# hoppercontroller.net
KiCad netlist of a schematic drawn in EAGLE
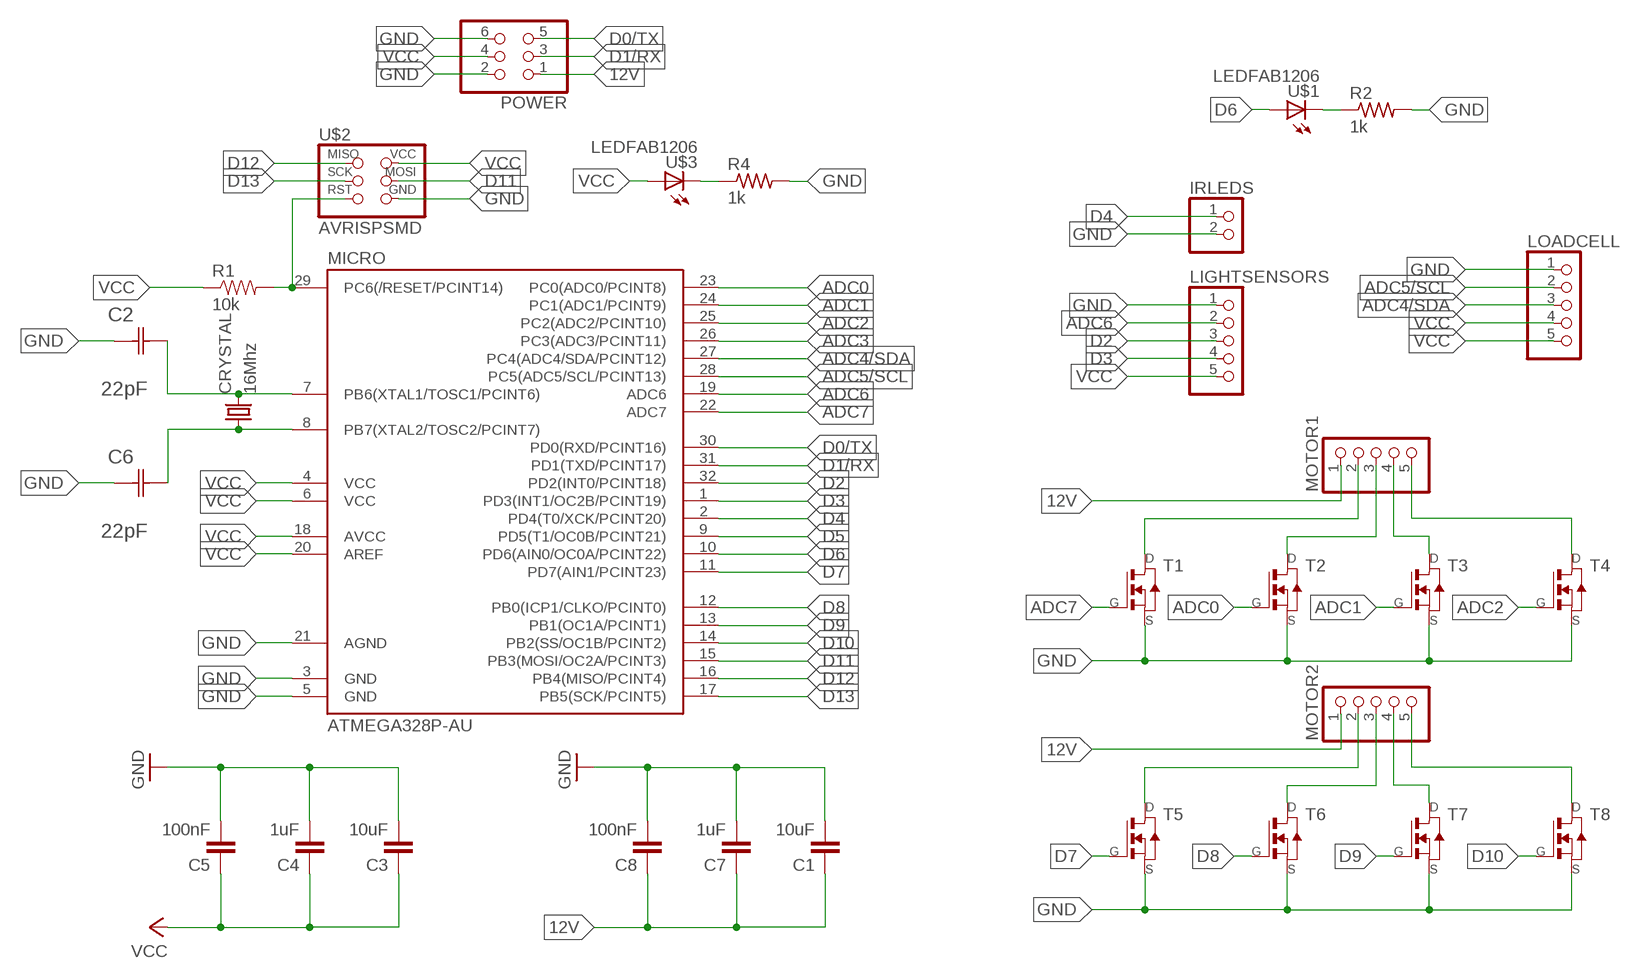
[diagram p0: schematic, sheet 1]

(export (version "E")
  (design (tool "Eeschema 10.0.6"))
  (components
    (comp (ref "C1")
      (value "10uF")
      (footprint "eagle-import:1206")
      (libsource (lib "eagle-import") (part "CAP1206"))
    )
    (comp (ref "C2")
      (value "22pF")
      (footprint "eagle-import:CAPC3216X178N")
      (fields (field (name "MPN") "0612ZC225MAT2A") (field (name "TOLERANCE") "±20%"))
      (libsource (lib "eagle-import") (part "0612ZC225MAT2A"))
    )
    (comp (ref "C3")
      (value "10uF")
      (footprint "eagle-import:1206")
      (libsource (lib "eagle-import") (part "CAP1206"))
    )
    (comp (ref "C4")
      (value "1uF")
      (footprint "eagle-import:1206")
      (libsource (lib "eagle-import") (part "CAP1206"))
    )
    (comp (ref "C5")
      (value "100nF")
      (footprint "eagle-import:1206")
      (libsource (lib "eagle-import") (part "CAP1206"))
    )
    (comp (ref "C6")
      (value "22pF")
      (footprint "eagle-import:CAPC3216X178N")
      (fields (field (name "MPN") "0612ZC225MAT2A") (field (name "TOLERANCE") "±20%"))
      (libsource (lib "eagle-import") (part "0612ZC225MAT2A"))
    )
    (comp (ref "C7")
      (value "1uF")
      (footprint "eagle-import:1206")
      (libsource (lib "eagle-import") (part "CAP1206"))
    )
    (comp (ref "C8")
      (value "100nF")
      (footprint "eagle-import:1206")
      (libsource (lib "eagle-import") (part "CAP1206"))
    )
    (comp (ref "CRYSTAL")
      (value "16Mhz")
      (footprint "eagle-import:CSM-7X-DU")
      (libsource (lib "eagle-import") (part "CSM-7X-DU"))
    )
    (comp (ref "IRLEDS")
      (value "PINHD-1X2")
      (footprint "eagle-import:1X02")
      (libsource (lib "eagle-import") (part "PINHD-1X2"))
    )
    (comp (ref "LIGHTSENSORS")
      (value "PINHD-1X5")
      (footprint "eagle-import:1X05")
      (libsource (lib "eagle-import") (part "PINHD-1X5"))
    )
    (comp (ref "LOADCELL")
      (value "PINHD-1X5")
      (footprint "eagle-import:1X05")
      (libsource (lib "eagle-import") (part "PINHD-1X5"))
    )
    (comp (ref "MICRO")
      (value "ATMEGA328P-AU")
      (footprint "eagle-import:TQFP32-08")
      (libsource (lib "eagle-import") (part "ATMEGA48/88/168-AU"))
    )
    (comp (ref "MOTOR1")
      (value "PINHD-1X5")
      (footprint "eagle-import:1X05")
      (libsource (lib "eagle-import") (part "PINHD-1X5"))
    )
    (comp (ref "MOTOR2")
      (value "PINHD-1X5")
      (footprint "eagle-import:1X05")
      (libsource (lib "eagle-import") (part "PINHD-1X5"))
    )
    (comp (ref "POWER")
      (value "PINHD-2X3-SMD")
      (footprint "eagle-import:2X03SMD")
      (libsource (lib "eagle-import") (part "PINHD-2X3-SMD"))
    )
    (comp (ref "R1")
      (value "10k")
      (footprint "eagle-import:1206")
      (libsource (lib "eagle-import") (part "RESISTOR1206"))
    )
    (comp (ref "R2")
      (value "1k")
      (footprint "eagle-import:R1206FAB")
      (libsource (lib "eagle-import") (part "RES-US1206FAB"))
    )
    (comp (ref "R4")
      (value "1k")
      (footprint "eagle-import:R1206FAB")
      (libsource (lib "eagle-import") (part "RES-US1206FAB"))
    )
    (comp (ref "T1")
      (value "NMOSFETTO252")
      (footprint "eagle-import:TO252")
      (libsource (lib "eagle-import") (part "NMOSFETTO252"))
    )
    (comp (ref "T2")
      (value "NMOSFETTO252")
      (footprint "eagle-import:TO252")
      (libsource (lib "eagle-import") (part "NMOSFETTO252"))
    )
    (comp (ref "T3")
      (value "NMOSFETTO252")
      (footprint "eagle-import:TO252")
      (libsource (lib "eagle-import") (part "NMOSFETTO252"))
    )
    (comp (ref "T4")
      (value "NMOSFETTO252")
      (footprint "eagle-import:TO252")
      (libsource (lib "eagle-import") (part "NMOSFETTO252"))
    )
    (comp (ref "T5")
      (value "NMOSFETTO252")
      (footprint "eagle-import:TO252")
      (libsource (lib "eagle-import") (part "NMOSFETTO252"))
    )
    (comp (ref "T6")
      (value "NMOSFETTO252")
      (footprint "eagle-import:TO252")
      (libsource (lib "eagle-import") (part "NMOSFETTO252"))
    )
    (comp (ref "T7")
      (value "NMOSFETTO252")
      (footprint "eagle-import:TO252")
      (libsource (lib "eagle-import") (part "NMOSFETTO252"))
    )
    (comp (ref "T8")
      (value "NMOSFETTO252")
      (footprint "eagle-import:TO252")
      (libsource (lib "eagle-import") (part "NMOSFETTO252"))
    )
    (comp (ref "U$1")
      (value "LEDFAB1206")
      (footprint "eagle-import:LED1206FAB")
      (libsource (lib "eagle-import") (part "LEDFAB1206"))
    )
    (comp (ref "U$2")
      (value "AVRISPSMD")
      (footprint "eagle-import:2X03SMD")
      (libsource (lib "eagle-import") (part "AVRISPSMD"))
    )
    (comp (ref "U$3")
      (value "LEDFAB1206")
      (footprint "eagle-import:LED1206FAB")
      (libsource (lib "eagle-import") (part "LEDFAB1206"))
    )
  )
  (nets
    (net (code "1") (name "12V") (class "Default")
      (node (ref "C1") (pin "1") (pinfunction "1_1") (pintype "passive"))
      (node (ref "C7") (pin "1") (pinfunction "1_1") (pintype "passive"))
      (node (ref "C8") (pin "1") (pinfunction "1_1") (pintype "passive"))
      (node (ref "MOTOR1") (pin "1") (pinfunction "1_1") (pintype "passive"))
      (node (ref "MOTOR2") (pin "1") (pinfunction "1_1") (pintype "passive"))
      (node (ref "POWER") (pin "1") (pinfunction "1_1") (pintype "passive"))
    )
    (net (code "2") (name "ADC0") (class "Default")
      (node (ref "MICRO") (pin "23") (pinfunction "PC0(ADC0/PCINT8)_23") (pintype "bidirectional"))
      (node (ref "T2") (pin "1") (pinfunction "G_1") (pintype "passive"))
    )
    (net (code "3") (name "ADC1") (class "Default")
      (node (ref "MICRO") (pin "24") (pinfunction "PC1(ADC1/PCINT9)_24") (pintype "bidirectional"))
      (node (ref "T3") (pin "1") (pinfunction "G_1") (pintype "passive"))
    )
    (net (code "4") (name "ADC2") (class "Default")
      (node (ref "MICRO") (pin "25") (pinfunction "PC2(ADC2/PCINT10)_25") (pintype "bidirectional"))
      (node (ref "T4") (pin "1") (pinfunction "G_1") (pintype "passive"))
    )
    (net (code "5") (name "ADC3") (class "Default")
      (node (ref "MICRO") (pin "26") (pinfunction "PC3(ADC3/PCINT11)_26") (pintype "bidirectional"))
    )
    (net (code "6") (name "ADC4{slash}SDA") (class "Default")
      (node (ref "LOADCELL") (pin "3") (pinfunction "3_3") (pintype "passive"))
      (node (ref "MICRO") (pin "27") (pinfunction "PC4(ADC4/SDA/PCINT12)_27") (pintype "bidirectional"))
    )
    (net (code "7") (name "ADC5{slash}SCL") (class "Default")
      (node (ref "LOADCELL") (pin "2") (pinfunction "2_2") (pintype "passive"))
      (node (ref "MICRO") (pin "28") (pinfunction "PC5(ADC5/SCL/PCINT13)_28") (pintype "bidirectional"))
    )
    (net (code "8") (name "ADC6") (class "Default")
      (node (ref "LIGHTSENSORS") (pin "2") (pinfunction "2_2") (pintype "passive"))
      (node (ref "MICRO") (pin "19") (pinfunction "ADC6_19") (pintype "passive"))
    )
    (net (code "9") (name "ADC7") (class "Default")
      (node (ref "MICRO") (pin "22") (pinfunction "ADC7_22") (pintype "passive"))
      (node (ref "T1") (pin "1") (pinfunction "G_1") (pintype "passive"))
    )
    (net (code "10") (name "D0{slash}TX") (class "Default")
      (node (ref "MICRO") (pin "30") (pinfunction "PD0(RXD/PCINT16)_30") (pintype "bidirectional"))
      (node (ref "POWER") (pin "5") (pinfunction "5_5") (pintype "passive"))
    )
    (net (code "11") (name "D1{slash}RX") (class "Default")
      (node (ref "MICRO") (pin "31") (pinfunction "PD1(TXD/PCINT17)_31") (pintype "bidirectional"))
      (node (ref "POWER") (pin "3") (pinfunction "3_3") (pintype "passive"))
    )
    (net (code "12") (name "D2") (class "Default")
      (node (ref "LIGHTSENSORS") (pin "3") (pinfunction "3_3") (pintype "passive"))
      (node (ref "MICRO") (pin "32") (pinfunction "PD2(INT0/PCINT18)_32") (pintype "bidirectional"))
    )
    (net (code "13") (name "D3") (class "Default")
      (node (ref "LIGHTSENSORS") (pin "4") (pinfunction "4_4") (pintype "passive"))
      (node (ref "MICRO") (pin "1") (pinfunction "PD3(INT1/OC2B/PCINT19)_1") (pintype "bidirectional"))
    )
    (net (code "14") (name "D4") (class "Default")
      (node (ref "IRLEDS") (pin "1") (pinfunction "1_1") (pintype "passive"))
      (node (ref "MICRO") (pin "2") (pinfunction "PD4(T0/XCK/PCINT20)_2") (pintype "bidirectional"))
    )
    (net (code "15") (name "D5") (class "Default")
      (node (ref "MICRO") (pin "9") (pinfunction "PD5(T1/OC0B/PCINT21)_9") (pintype "bidirectional"))
    )
    (net (code "16") (name "D6") (class "Default")
      (node (ref "MICRO") (pin "10") (pinfunction "PD6(AIN0/OC0A/PCINT22)_10") (pintype "bidirectional"))
      (node (ref "U$1") (pin "1") (pinfunction "A_1") (pintype "passive"))
    )
    (net (code "17") (name "D7") (class "Default")
      (node (ref "MICRO") (pin "11") (pinfunction "PD7(AIN1/PCINT23)_11") (pintype "bidirectional"))
      (node (ref "T5") (pin "1") (pinfunction "G_1") (pintype "passive"))
    )
    (net (code "18") (name "D8") (class "Default")
      (node (ref "MICRO") (pin "12") (pinfunction "PB0(ICP1/CLKO/PCINT0)_12") (pintype "bidirectional"))
      (node (ref "T6") (pin "1") (pinfunction "G_1") (pintype "passive"))
    )
    (net (code "19") (name "D9") (class "Default")
      (node (ref "MICRO") (pin "13") (pinfunction "PB1(OC1A/PCINT1)_13") (pintype "bidirectional"))
      (node (ref "T7") (pin "1") (pinfunction "G_1") (pintype "passive"))
    )
    (net (code "20") (name "D10") (class "Default")
      (node (ref "MICRO") (pin "14") (pinfunction "PB2(SS/OC1B/PCINT2)_14") (pintype "bidirectional"))
      (node (ref "T8") (pin "1") (pinfunction "G_1") (pintype "passive"))
    )
    (net (code "21") (name "D11") (class "Default")
      (node (ref "MICRO") (pin "15") (pinfunction "PB3(MOSI/OC2A/PCINT3)_15") (pintype "bidirectional"))
      (node (ref "U$2") (pin "4") (pinfunction "MOSI_4") (pintype "passive"))
    )
    (net (code "22") (name "D12") (class "Default")
      (node (ref "MICRO") (pin "16") (pinfunction "PB4(MISO/PCINT4)_16") (pintype "bidirectional"))
      (node (ref "U$2") (pin "1") (pinfunction "MISO_1") (pintype "passive"))
    )
    (net (code "23") (name "D13") (class "Default")
      (node (ref "MICRO") (pin "17") (pinfunction "PB5(SCK/PCINT5)_17") (pintype "bidirectional"))
      (node (ref "U$2") (pin "3") (pinfunction "SCK_3") (pintype "passive"))
    )
    (net (code "24") (name "GND") (class "Default")
      (node (ref "C1") (pin "2") (pinfunction "2_2") (pintype "passive"))
      (node (ref "C2") (pin "1") (pinfunction "C1_1") (pintype "passive"))
      (node (ref "C3") (pin "2") (pinfunction "2_2") (pintype "passive"))
      (node (ref "C4") (pin "2") (pinfunction "2_2") (pintype "passive"))
      (node (ref "C5") (pin "2") (pinfunction "2_2") (pintype "passive"))
      (node (ref "C6") (pin "1") (pinfunction "C1_1") (pintype "passive"))
      (node (ref "C7") (pin "2") (pinfunction "2_2") (pintype "passive"))
      (node (ref "C8") (pin "2") (pinfunction "2_2") (pintype "passive"))
      (node (ref "IRLEDS") (pin "2") (pinfunction "2_2") (pintype "passive"))
      (node (ref "LIGHTSENSORS") (pin "1") (pinfunction "1_1") (pintype "passive"))
      (node (ref "LOADCELL") (pin "1") (pinfunction "1_1") (pintype "passive"))
      (node (ref "MICRO") (pin "21") (pinfunction "AGND_21") (pintype "power_in"))
      (node (ref "MICRO") (pin "3") (pinfunction "GND_3") (pintype "power_in"))
      (node (ref "MICRO") (pin "5") (pinfunction "GND_5") (pintype "power_in"))
      (node (ref "POWER") (pin "2") (pinfunction "2_2") (pintype "passive"))
      (node (ref "POWER") (pin "6") (pinfunction "6_6") (pintype "passive"))
      (node (ref "R2") (pin "2") (pinfunction "2_2") (pintype "passive"))
      (node (ref "R4") (pin "2") (pinfunction "2_2") (pintype "passive"))
      (node (ref "T1") (pin "2") (pinfunction "S_2") (pintype "passive"))
      (node (ref "T2") (pin "2") (pinfunction "S_2") (pintype "passive"))
      (node (ref "T3") (pin "2") (pinfunction "S_2") (pintype "passive"))
      (node (ref "T4") (pin "2") (pinfunction "S_2") (pintype "passive"))
      (node (ref "T5") (pin "2") (pinfunction "S_2") (pintype "passive"))
      (node (ref "T6") (pin "2") (pinfunction "S_2") (pintype "passive"))
      (node (ref "T7") (pin "2") (pinfunction "S_2") (pintype "passive"))
      (node (ref "T8") (pin "2") (pinfunction "S_2") (pintype "passive"))
      (node (ref "U$2") (pin "6") (pinfunction "GND_6") (pintype "passive"))
    )
    (net (code "25") (name "Net-(C2-C2)") (class "Default")
      (node (ref "C2") (pin "2") (pinfunction "C2_2") (pintype "passive"))
      (node (ref "CRYSTAL") (pin "2") (pinfunction "2_2") (pintype "passive"))
      (node (ref "MICRO") (pin "7") (pinfunction "PB6(XTAL1/TOSC1/PCINT6)_7") (pintype "bidirectional"))
    )
    (net (code "26") (name "Net-(C6-C2)") (class "Default")
      (node (ref "C6") (pin "2") (pinfunction "C2_2") (pintype "passive"))
      (node (ref "CRYSTAL") (pin "1") (pinfunction "1_1") (pintype "passive"))
      (node (ref "MICRO") (pin "8") (pinfunction "PB7(XTAL2/TOSC2/PCINT7)_8") (pintype "bidirectional"))
    )
    (net (code "27") (name "Net-(MICRO-PC6({slash}RESET{slash}PCINT14))") (class "Default")
      (node (ref "MICRO") (pin "29") (pinfunction "PC6(/RESET/PCINT14)_29") (pintype "bidirectional"))
      (node (ref "R1") (pin "2") (pinfunction "2_2") (pintype "passive"))
      (node (ref "U$2") (pin "5") (pinfunction "RST_5") (pintype "passive"))
    )
    (net (code "28") (name "Net-(T1-D)") (class "Default")
      (node (ref "MOTOR1") (pin "2") (pinfunction "2_2") (pintype "passive"))
      (node (ref "T1") (pin "3") (pinfunction "D_3") (pintype "passive"))
    )
    (net (code "29") (name "Net-(T2-D)") (class "Default")
      (node (ref "MOTOR1") (pin "3") (pinfunction "3_3") (pintype "passive"))
      (node (ref "T2") (pin "3") (pinfunction "D_3") (pintype "passive"))
    )
    (net (code "30") (name "Net-(T3-D)") (class "Default")
      (node (ref "MOTOR1") (pin "4") (pinfunction "4_4") (pintype "passive"))
      (node (ref "T3") (pin "3") (pinfunction "D_3") (pintype "passive"))
    )
    (net (code "31") (name "Net-(T4-D)") (class "Default")
      (node (ref "MOTOR1") (pin "5") (pinfunction "5_5") (pintype "passive"))
      (node (ref "T4") (pin "3") (pinfunction "D_3") (pintype "passive"))
    )
    (net (code "32") (name "Net-(T5-D)") (class "Default")
      (node (ref "MOTOR2") (pin "2") (pinfunction "2_2") (pintype "passive"))
      (node (ref "T5") (pin "3") (pinfunction "D_3") (pintype "passive"))
    )
    (net (code "33") (name "Net-(T6-D)") (class "Default")
      (node (ref "MOTOR2") (pin "3") (pinfunction "3_3") (pintype "passive"))
      (node (ref "T6") (pin "3") (pinfunction "D_3") (pintype "passive"))
    )
    (net (code "34") (name "Net-(T7-D)") (class "Default")
      (node (ref "MOTOR2") (pin "4") (pinfunction "4_4") (pintype "passive"))
      (node (ref "T7") (pin "3") (pinfunction "D_3") (pintype "passive"))
    )
    (net (code "35") (name "Net-(T8-D)") (class "Default")
      (node (ref "MOTOR2") (pin "5") (pinfunction "5_5") (pintype "passive"))
      (node (ref "T8") (pin "3") (pinfunction "D_3") (pintype "passive"))
    )
    (net (code "36") (name "Net-(U$1-C)") (class "Default")
      (node (ref "R2") (pin "1") (pinfunction "1_1") (pintype "passive"))
      (node (ref "U$1") (pin "2") (pinfunction "C_2") (pintype "passive"))
    )
    (net (code "37") (name "Net-(U$3-C)") (class "Default")
      (node (ref "R4") (pin "1") (pinfunction "1_1") (pintype "passive"))
      (node (ref "U$3") (pin "2") (pinfunction "C_2") (pintype "passive"))
    )
    (net (code "38") (name "VCC") (class "Default")
      (node (ref "C3") (pin "1") (pinfunction "1_1") (pintype "passive"))
      (node (ref "C4") (pin "1") (pinfunction "1_1") (pintype "passive"))
      (node (ref "C5") (pin "1") (pinfunction "1_1") (pintype "passive"))
      (node (ref "LIGHTSENSORS") (pin "5") (pinfunction "5_5") (pintype "passive"))
      (node (ref "LOADCELL") (pin "4") (pinfunction "4_4") (pintype "passive"))
      (node (ref "LOADCELL") (pin "5") (pinfunction "5_5") (pintype "passive"))
      (node (ref "MICRO") (pin "18") (pinfunction "AVCC_18") (pintype "passive"))
      (node (ref "MICRO") (pin "20") (pinfunction "AREF_20") (pintype "passive"))
      (node (ref "MICRO") (pin "4") (pinfunction "VCC_4") (pintype "power_in"))
      (node (ref "MICRO") (pin "6") (pinfunction "VCC_6") (pintype "power_in"))
      (node (ref "POWER") (pin "4") (pinfunction "4_4") (pintype "passive"))
      (node (ref "R1") (pin "1") (pinfunction "1_1") (pintype "passive"))
      (node (ref "U$2") (pin "2") (pinfunction "VCC_2") (pintype "passive"))
      (node (ref "U$3") (pin "1") (pinfunction "A_1") (pintype "passive"))
    )
  )
)
